# wheelmotor_connections.net
KiCad netlist of a schematic drawn in Altium Designer
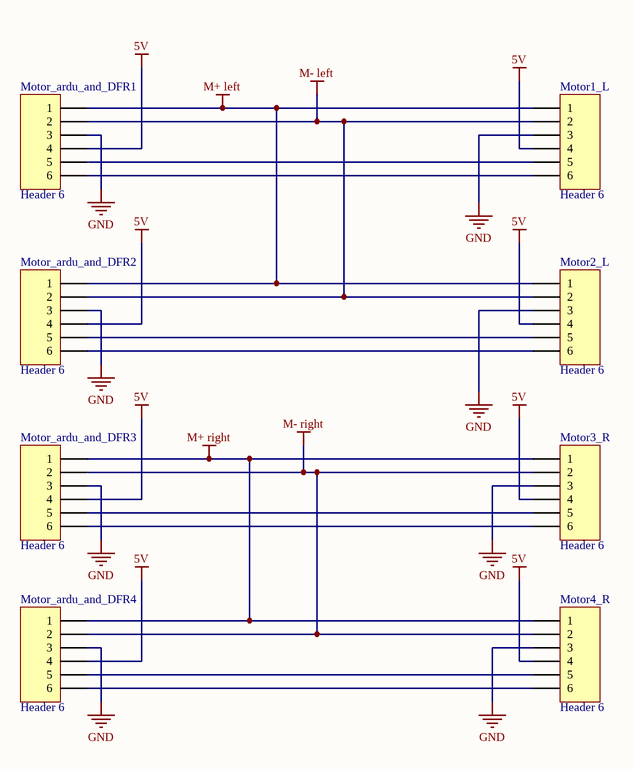
[diagram p0: wheelmotor_connections.SchDoc]

(export (version "E")
  (design (tool "Eeschema 10.0.6"))
  (components
    (comp (ref "Motor1_L")
      (value "Header 6")
      (footprint "HDR1X6")
      (description "Header, 6-Pin")
      (fields (field (name "PUBLISHER") "Altium Limited"))
      (libsource (lib "") (part "Header 6_1"))
    )
    (comp (ref "Motor2_L")
      (value "Header 6")
      (footprint "HDR1X6")
      (description "Header, 6-Pin")
      (fields (field (name "PUBLISHER") "Altium Limited"))
      (libsource (lib "") (part "Header 6_1"))
    )
    (comp (ref "Motor3_R")
      (value "Header 6")
      (footprint "HDR1X6")
      (description "Header, 6-Pin")
      (fields (field (name "PUBLISHER") "Altium Limited"))
      (libsource (lib "") (part "Header 6_1"))
    )
    (comp (ref "Motor4_R")
      (value "Header 6")
      (footprint "HDR1X6")
      (description "Header, 6-Pin")
      (fields (field (name "PUBLISHER") "Altium Limited"))
      (libsource (lib "") (part "Header 6_1"))
    )
    (comp (ref "Motor_ardu_and_DFR1")
      (value "Header 6")
      (footprint "HDR1X6")
      (description "Header, 6-Pin")
      (fields (field (name "PUBLISHER") "Altium Limited"))
      (libsource (lib "Miscellaneous Connectors") (part "Header 6"))
    )
    (comp (ref "Motor_ardu_and_DFR2")
      (value "Header 6")
      (footprint "HDR1X6")
      (description "Header, 6-Pin")
      (fields (field (name "PUBLISHER") "Altium Limited"))
      (libsource (lib "Miscellaneous Connectors") (part "Header 6"))
    )
    (comp (ref "Motor_ardu_and_DFR3")
      (value "Header 6")
      (footprint "HDR1X6")
      (description "Header, 6-Pin")
      (fields (field (name "PUBLISHER") "Altium Limited"))
      (libsource (lib "Miscellaneous Connectors") (part "Header 6"))
    )
    (comp (ref "Motor_ardu_and_DFR4")
      (value "Header 6")
      (footprint "HDR1X6")
      (description "Header, 6-Pin")
      (fields (field (name "PUBLISHER") "Altium Limited"))
      (libsource (lib "Miscellaneous Connectors") (part "Header 6"))
    )
  )
  (nets
    (net (code "1") (name "5V") (class "Default")
      (node (ref "Motor1_L") (pin "4") (pinfunction "4_4") (pintype "passive"))
      (node (ref "Motor2_L") (pin "4") (pinfunction "4_4") (pintype "passive"))
      (node (ref "Motor3_R") (pin "4") (pinfunction "4_4") (pintype "passive"))
      (node (ref "Motor4_R") (pin "4") (pinfunction "4_4") (pintype "passive"))
      (node (ref "Motor_ardu_and_DFR1") (pin "4") (pinfunction "4_4") (pintype "passive"))
      (node (ref "Motor_ardu_and_DFR2") (pin "4") (pinfunction "4_4") (pintype "passive"))
      (node (ref "Motor_ardu_and_DFR3") (pin "4") (pinfunction "4_4") (pintype "passive"))
      (node (ref "Motor_ardu_and_DFR4") (pin "4") (pinfunction "4_4") (pintype "passive"))
    )
    (net (code "2") (name "GND") (class "Default")
      (node (ref "Motor1_L") (pin "3") (pinfunction "3_3") (pintype "passive"))
      (node (ref "Motor2_L") (pin "3") (pinfunction "3_3") (pintype "passive"))
      (node (ref "Motor3_R") (pin "3") (pinfunction "3_3") (pintype "passive"))
      (node (ref "Motor4_R") (pin "3") (pinfunction "3_3") (pintype "passive"))
      (node (ref "Motor_ardu_and_DFR1") (pin "3") (pinfunction "3_3") (pintype "passive"))
      (node (ref "Motor_ardu_and_DFR2") (pin "3") (pinfunction "3_3") (pintype "passive"))
      (node (ref "Motor_ardu_and_DFR3") (pin "3") (pinfunction "3_3") (pintype "passive"))
      (node (ref "Motor_ardu_and_DFR4") (pin "3") (pinfunction "3_3") (pintype "passive"))
    )
    (net (code "3") (name "M+ left") (class "Default")
      (node (ref "Motor1_L") (pin "1") (pinfunction "1_1") (pintype "passive"))
      (node (ref "Motor2_L") (pin "1") (pinfunction "1_1") (pintype "passive"))
      (node (ref "Motor_ardu_and_DFR1") (pin "1") (pinfunction "1_1") (pintype "passive"))
      (node (ref "Motor_ardu_and_DFR2") (pin "1") (pinfunction "1_1") (pintype "passive"))
    )
    (net (code "4") (name "M+ right") (class "Default")
      (node (ref "Motor3_R") (pin "1") (pinfunction "1_1") (pintype "passive"))
      (node (ref "Motor4_R") (pin "1") (pinfunction "1_1") (pintype "passive"))
      (node (ref "Motor_ardu_and_DFR3") (pin "1") (pinfunction "1_1") (pintype "passive"))
      (node (ref "Motor_ardu_and_DFR4") (pin "1") (pinfunction "1_1") (pintype "passive"))
    )
    (net (code "5") (name "M- left") (class "Default")
      (node (ref "Motor1_L") (pin "2") (pinfunction "2_2") (pintype "passive"))
      (node (ref "Motor2_L") (pin "2") (pinfunction "2_2") (pintype "passive"))
      (node (ref "Motor_ardu_and_DFR1") (pin "2") (pinfunction "2_2") (pintype "passive"))
      (node (ref "Motor_ardu_and_DFR2") (pin "2") (pinfunction "2_2") (pintype "passive"))
    )
    (net (code "6") (name "M- right") (class "Default")
      (node (ref "Motor3_R") (pin "2") (pinfunction "2_2") (pintype "passive"))
      (node (ref "Motor4_R") (pin "2") (pinfunction "2_2") (pintype "passive"))
      (node (ref "Motor_ardu_and_DFR3") (pin "2") (pinfunction "2_2") (pintype "passive"))
      (node (ref "Motor_ardu_and_DFR4") (pin "2") (pinfunction "2_2") (pintype "passive"))
    )
    (net (code "7") (name "Net-(Motor1_L-Pad5)") (class "Default")
      (node (ref "Motor1_L") (pin "5") (pinfunction "5_5") (pintype "passive"))
      (node (ref "Motor_ardu_and_DFR1") (pin "5") (pinfunction "5_5") (pintype "passive"))
    )
    (net (code "8") (name "Net-(Motor1_L-Pad6)") (class "Default")
      (node (ref "Motor1_L") (pin "6") (pinfunction "6_6") (pintype "passive"))
      (node (ref "Motor_ardu_and_DFR1") (pin "6") (pinfunction "6_6") (pintype "passive"))
    )
    (net (code "9") (name "Net-(Motor2_L-Pad5)") (class "Default")
      (node (ref "Motor2_L") (pin "5") (pinfunction "5_5") (pintype "passive"))
      (node (ref "Motor_ardu_and_DFR2") (pin "5") (pinfunction "5_5") (pintype "passive"))
    )
    (net (code "10") (name "Net-(Motor2_L-Pad6)") (class "Default")
      (node (ref "Motor2_L") (pin "6") (pinfunction "6_6") (pintype "passive"))
      (node (ref "Motor_ardu_and_DFR2") (pin "6") (pinfunction "6_6") (pintype "passive"))
    )
    (net (code "11") (name "Net-(Motor3_R-Pad5)") (class "Default")
      (node (ref "Motor3_R") (pin "5") (pinfunction "5_5") (pintype "passive"))
      (node (ref "Motor_ardu_and_DFR3") (pin "5") (pinfunction "5_5") (pintype "passive"))
    )
    (net (code "12") (name "Net-(Motor3_R-Pad6)") (class "Default")
      (node (ref "Motor3_R") (pin "6") (pinfunction "6_6") (pintype "passive"))
      (node (ref "Motor_ardu_and_DFR3") (pin "6") (pinfunction "6_6") (pintype "passive"))
    )
    (net (code "13") (name "Net-(Motor4_R-Pad5)") (class "Default")
      (node (ref "Motor4_R") (pin "5") (pinfunction "5_5") (pintype "passive"))
      (node (ref "Motor_ardu_and_DFR4") (pin "5") (pinfunction "5_5") (pintype "passive"))
    )
    (net (code "14") (name "Net-(Motor4_R-Pad6)") (class "Default")
      (node (ref "Motor4_R") (pin "6") (pinfunction "6_6") (pintype "passive"))
      (node (ref "Motor_ardu_and_DFR4") (pin "6") (pinfunction "6_6") (pintype "passive"))
    )
  )
)
